# DIO_MCX_Supply.net
KiCad netlist of a schematic drawn in Altium Designer
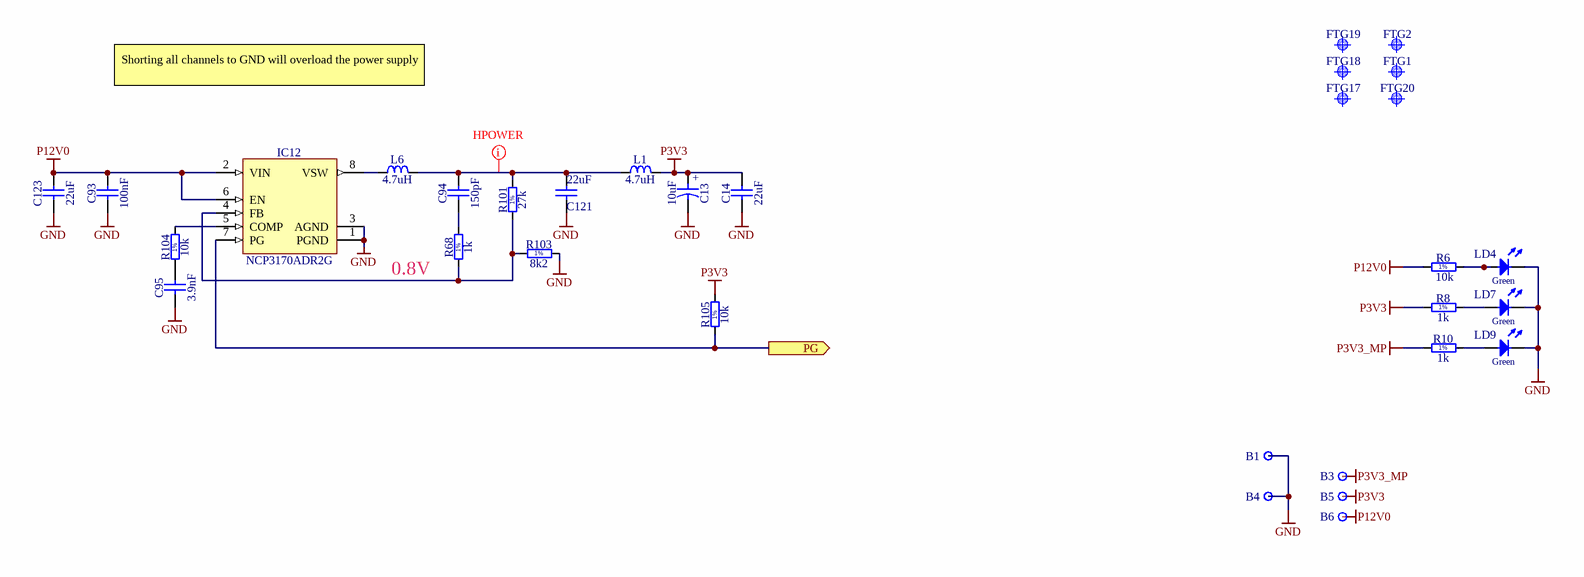
[diagram p0: DIO_MCX_Supply.SchDoc]

(export (version "E")
  (design (tool "Eeschema 10.0.6"))
  (components
    (comp (ref "B1")
      (value "Plated Hole")
      (footprint "c130h60")
      (description "Single Terminal Socket")
      (fields (field (name "PART NUMBER") "PLATED_HOLE0.6_PAD1.3") (field (name "AUTHOR") "CERN DEM MR"))
      (libsource (lib "Eletro-mechanical") (part "Single Terminal Socket"))
    )
    (comp (ref "B3")
      (value "Plated Hole")
      (footprint "c130h60")
      (description "Single Terminal Socket")
      (fields (field (name "PART NUMBER") "PLATED_HOLE0.6_PAD1.3") (field (name "AUTHOR") "CERN DEM MR"))
      (libsource (lib "Eletro-mechanical") (part "Single Terminal Socket"))
    )
    (comp (ref "B4")
      (value "Plated Hole")
      (footprint "c130h60")
      (description "Single Terminal Socket")
      (fields (field (name "PART NUMBER") "PLATED_HOLE0.6_PAD1.3") (field (name "AUTHOR") "CERN DEM MR"))
      (libsource (lib "Eletro-mechanical") (part "Single Terminal Socket"))
    )
    (comp (ref "B5")
      (value "Plated Hole")
      (footprint "c130h60")
      (description "Single Terminal Socket")
      (fields (field (name "PART NUMBER") "PLATED_HOLE0.6_PAD1.3") (field (name "AUTHOR") "CERN DEM MR"))
      (libsource (lib "Eletro-mechanical") (part "Single Terminal Socket"))
    )
    (comp (ref "B6")
      (value "Plated Hole")
      (footprint "c130h60")
      (description "Single Terminal Socket")
      (fields (field (name "PART NUMBER") "PLATED_HOLE0.6_PAD1.3") (field (name "AUTHOR") "CERN DEM MR"))
      (libsource (lib "Eletro-mechanical") (part "Single Terminal Socket"))
    )
    (comp (ref "C13")
      (value "10uF")
      (footprint "CAPAE430X540N")
      (description "Polarised capacitor")
      (fields
        (field (name "PART NUMBER") "CAE430-540_10UF_16V_20%")
        (field (name "VOLTAGE") "16V")
        (field (name "AUTHOR") "CERN DEM JLC")
      )
      (libsource (lib "Capacitors") (part "Capacitor - polarized"))
    )
    (comp (ref "C14")
      (value "22uF")
      (footprint "CAPC2012X135N")
      (description "Non-polarised capacitor")
      (fields
        (field (name "PART NUMBER") "CC0805_22UF_16V_10%_X5R")
        (field (name "VOLTAGE") "16V")
        (field (name "AUTHOR") "CERN DEM JLC")
      )
      (libsource (lib "Capacitors") (part "Capacitor - non polarized"))
    )
    (comp (ref "C93")
      (value "100nF")
      (footprint "CAPC1005X55N")
      (description "Non-polarised capacitor")
      (fields
        (field (name "PART NUMBER") "CC0402_100NF_16V_10%_X5R")
        (field (name "VOLTAGE") "16V")
        (field (name "AUTHOR") "CERN DEM JLC")
      )
      (libsource (lib "Capacitors") (part "Capacitor - non polarized"))
    )
    (comp (ref "C94")
      (value "150pF")
      (footprint "CAPC1608X87N")
      (description "Non-polarised capacitor")
      (fields
        (field (name "PART NUMBER") "CC0603_150PF_50V_1%_NP0")
        (field (name "VOLTAGE") "50V")
        (field (name "AUTHOR") "CERN DEM MR")
      )
      (libsource (lib "Capacitors") (part "Capacitor - non polarized"))
    )
    (comp (ref "C95")
      (value "3.9nF")
      (footprint "CAPC1608X87N")
      (description "Non-polarised capacitor")
      (fields
        (field (name "PART NUMBER") "CC0603_3.9NF_50V_5%_X7R")
        (field (name "VOLTAGE") "50V")
        (field (name "AUTHOR") "CERN DEM JLC")
      )
      (libsource (lib "Capacitors") (part "Capacitor - non polarized"))
    )
    (comp (ref "C121")
      (value "22uF")
      (footprint "CAPC2012X135N")
      (description "Non-polarised capacitor")
      (fields
        (field (name "PART NUMBER") "CC0805_22UF_16V_10%_X5R")
        (field (name "VOLTAGE") "16V")
        (field (name "AUTHOR") "CERN DEM JLC")
      )
      (libsource (lib "Capacitors") (part "Capacitor - non polarized"))
    )
    (comp (ref "C123")
      (value "22uF")
      (footprint "CAPC2012X135N")
      (description "Non-polarised capacitor")
      (fields
        (field (name "PART NUMBER") "CC0805_22UF_16V_10%_X5R")
        (field (name "VOLTAGE") "16V")
        (field (name "AUTHOR") "CERN DEM JLC")
      )
      (libsource (lib "Capacitors") (part "Capacitor - non polarized"))
    )
    (comp (ref "FTG1")
      (value "Use only in PCB")
      (footprint "FIDUCIAL_TOP_C100-200")
      (description "Fiducial Target")
      (fields (field (name "PART NUMBER") "FIDUCIAL_TARGET_C100-200") (field (name "AUTHOR") "CERN DEM JLC"))
      (libsource (lib "Eletro-mechanical") (part "Fiducial Target"))
    )
    (comp (ref "FTG2")
      (value "Use only in PCB")
      (footprint "FIDUCIAL_TOP_C100-200")
      (description "Fiducial Target")
      (fields (field (name "PART NUMBER") "FIDUCIAL_TARGET_C100-200") (field (name "AUTHOR") "CERN DEM JLC"))
      (libsource (lib "Eletro-mechanical") (part "Fiducial Target"))
    )
    (comp (ref "FTG17")
      (value "Use only in PCB")
      (footprint "FIDUCIAL_TOP_C100-200")
      (description "Fiducial Target")
      (fields (field (name "PART NUMBER") "FIDUCIAL_TARGET_C100-200") (field (name "AUTHOR") "CERN DEM JLC"))
      (libsource (lib "Eletro-mechanical") (part "Fiducial Target"))
    )
    (comp (ref "FTG18")
      (value "Use only in PCB")
      (footprint "FIDUCIAL_TOP_S100-200")
      (description "Fiducial Target")
      (fields (field (name "PART NUMBER") "FIDUCIAL_TARGET_S100-200") (field (name "AUTHOR") "CERN DEM JLC"))
      (libsource (lib "Eletro-mechanical") (part "Fiducial Target"))
    )
    (comp (ref "FTG19")
      (value "Use only in PCB")
      (footprint "FIDUCIAL_TOP_S100-200")
      (description "Fiducial Target")
      (fields (field (name "PART NUMBER") "FIDUCIAL_TARGET_S100-200") (field (name "AUTHOR") "CERN DEM JLC"))
      (libsource (lib "Eletro-mechanical") (part "Fiducial Target"))
    )
    (comp (ref "FTG20")
      (value "Use only in PCB")
      (footprint "FIDUCIAL_TOP_S100-200")
      (description "Fiducial Target")
      (fields (field (name "PART NUMBER") "FIDUCIAL_TARGET_S100-200") (field (name "AUTHOR") "CERN DEM JLC"))
      (libsource (lib "Eletro-mechanical") (part "Fiducial Target"))
    )
    (comp (ref "IC12")
      (value "NCP3170ADR2G")
      (footprint "SOIC127P600X175-8N")
      (description "Synchronous PWM Switching Converter")
      (fields (field (name "MANUFACTURER") "ON SEMICONDUCTOR") (field (name "AUTHOR") "CERN DEM MR"))
      (libsource (lib "ICs And Semiconductors") (part "NCP3170ADR2G"))
    )
    (comp (ref "L1")
      (value "4.7uH")
      (footprint "IND_BOURNS_SRU8043")
      (description "Power Shielded  4.7uH 30% 4.6A")
      (fields
        (field (name "PART NUMBER") "IND_4.7UH_30%_BOURNS_SRU8043")
        (field (name "POWER") "4.6A")
        (field (name "AUTHOR") "GK")
      )
      (libsource (lib "Inductors_Transformers") (part "IND_4.7UH_30%_BOURNS_SRU8043"))
    )
    (comp (ref "L6")
      (value "4.7uH")
      (footprint "IND_BOURNS_SRU8043")
      (description "Power Shielded  4.7uH 30% 4.6A")
      (fields
        (field (name "PART NUMBER") "IND_4.7UH_30%_BOURNS_SRU8043")
        (field (name "POWER") "4.6A")
        (field (name "AUTHOR") "GK")
      )
      (libsource (lib "Inductors_Transformers") (part "IND_4.7UH_30%_BOURNS_SRU8043"))
    )
    (comp (ref "LD4")
      (value "Green")
      (footprint "LED_KINGBRIGHT_KPH-1608CGCK")
      (description "LED Green 1C 2A")
      (fields
        (field (name "PART NUMBER") "LED_KINGBRIGHT_KPH-1608CGCK")
        (field (name "MANUFACTURER") "KINGBRIGHT")
        (field (name "AUTHOR") "CERN DEM JLC")
      )
      (libsource (lib "ICs And Semiconductors") (part "LED Green 1C 2A"))
    )
    (comp (ref "LD7")
      (value "Green")
      (footprint "LED_KINGBRIGHT_KPH-1608CGCK")
      (description "LED Green 1C 2A")
      (fields
        (field (name "PART NUMBER") "LED_KINGBRIGHT_KPH-1608CGCK")
        (field (name "MANUFACTURER") "KINGBRIGHT")
        (field (name "AUTHOR") "CERN DEM JLC")
      )
      (libsource (lib "ICs And Semiconductors") (part "LED Green 1C 2A"))
    )
    (comp (ref "LD9")
      (value "Green")
      (footprint "LED_KINGBRIGHT_KPH-1608CGCK")
      (description "LED Green 1C 2A")
      (fields
        (field (name "PART NUMBER") "LED_KINGBRIGHT_KPH-1608CGCK")
        (field (name "MANUFACTURER") "KINGBRIGHT")
        (field (name "AUTHOR") "CERN DEM JLC")
      )
      (libsource (lib "ICs And Semiconductors") (part "LED Green 1C 2A"))
    )
    (comp (ref "R6")
      (value "10k")
      (footprint "RESC1005X40N")
      (description "Resistor - 1%")
      (fields
        (field (name "PART NUMBER") "R0402_10K_1%_0.0625W_100PPM")
        (field (name "POWER") "0.0625W")
        (field (name "AUTHOR") "CERN DEM JLC")
      )
      (libsource (lib "Resistors") (part "Resistor - 1%"))
    )
    (comp (ref "R8")
      (value "1k")
      (footprint "RESC1005X40N")
      (description "Resistor - 1%")
      (fields
        (field (name "PART NUMBER") "R0402_1K_1%_0.0625W_100PPM")
        (field (name "POWER") "0.0625W")
        (field (name "AUTHOR") "CERN DEM JLC")
      )
      (libsource (lib "Resistors") (part "Resistor - 1%"))
    )
    (comp (ref "R10")
      (value "1k")
      (footprint "RESC1005X40N")
      (description "Resistor - 1%")
      (fields
        (field (name "PART NUMBER") "R0402_1K_1%_0.0625W_100PPM")
        (field (name "POWER") "0.0625W")
        (field (name "AUTHOR") "CERN DEM JLC")
      )
      (libsource (lib "Resistors") (part "Resistor - 1%"))
    )
    (comp (ref "R68")
      (value "1k")
      (footprint "RESC1005X40N")
      (description "Resistor - 1%")
      (fields
        (field (name "PART NUMBER") "R0402_1K_1%_0.0625W_100PPM")
        (field (name "POWER") "0.0625W")
        (field (name "AUTHOR") "CERN DEM JLC")
      )
      (libsource (lib "Resistors") (part "Resistor - 1%"))
    )
    (comp (ref "R101")
      (value "27k")
      (footprint "RESC1005X40N")
      (description "Resistor - 1%")
      (fields
        (field (name "PART NUMBER") "R0402_27K_1%_0.0625W_100PPM")
        (field (name "POWER") "0.0625W")
        (field (name "AUTHOR") "CERN DEM JLC")
      )
      (libsource (lib "Resistors") (part "Resistor - 1%"))
    )
    (comp (ref "R103")
      (value "8k2")
      (footprint "RESC1005X40N")
      (description "Resistor - 1%")
      (fields
        (field (name "PART NUMBER") "R0402_8K2_1%_0.0625W_100PPM")
        (field (name "POWER") "0.0625W")
        (field (name "AUTHOR") "CERN DEM JLC")
      )
      (libsource (lib "Resistors") (part "Resistor - 1%"))
    )
    (comp (ref "R104")
      (value "10k")
      (footprint "RESC1005X40N")
      (description "Resistor - 1%")
      (fields
        (field (name "PART NUMBER") "R0402_10K_1%_0.0625W_100PPM")
        (field (name "POWER") "0.0625W")
        (field (name "AUTHOR") "CERN DEM JLC")
      )
      (libsource (lib "Resistors") (part "Resistor - 1%"))
    )
    (comp (ref "R105")
      (value "10k")
      (footprint "RESC1005X40N")
      (description "Resistor - 1%")
      (fields
        (field (name "PART NUMBER") "R0402_10K_1%_0.0625W_100PPM")
        (field (name "POWER") "0.0625W")
        (field (name "AUTHOR") "CERN DEM JLC")
      )
      (libsource (lib "Resistors") (part "Resistor - 1%"))
    )
  )
  (nets
    (net (code "1") (name "/PG") (class "Default")
      (node (ref "IC12") (pin "7") (pinfunction "PG_7") (pintype "input"))
      (node (ref "R105") (pin "1") (pinfunction "1_1") (pintype "passive"))
    )
    (net (code "2") (name "GND") (class "Default")
      (node (ref "B1") (pin "1") (pinfunction "1_1") (pintype "bidirectional"))
      (node (ref "B4") (pin "1") (pinfunction "1_1") (pintype "bidirectional"))
      (node (ref "C121") (pin "1") (pinfunction "1_1") (pintype "passive"))
      (node (ref "C123") (pin "1") (pinfunction "1_1") (pintype "passive"))
      (node (ref "C13") (pin "2") (pinfunction "2_2") (pintype "passive"))
      (node (ref "C14") (pin "1") (pinfunction "1_1") (pintype "passive"))
      (node (ref "C93") (pin "1") (pinfunction "1_1") (pintype "passive"))
      (node (ref "C95") (pin "1") (pinfunction "1_1") (pintype "passive"))
      (node (ref "IC12") (pin "1") (pinfunction "PGND_1") (pintype "power_in"))
      (node (ref "IC12") (pin "3") (pinfunction "AGND_3") (pintype "power_in"))
      (node (ref "LD4") (pin "1") (pinfunction "C_1") (pintype "passive"))
      (node (ref "LD7") (pin "1") (pinfunction "C_1") (pintype "passive"))
      (node (ref "LD9") (pin "1") (pinfunction "C_1") (pintype "passive"))
      (node (ref "R103") (pin "2") (pinfunction "2_2") (pintype "passive"))
    )
    (net (code "3") (name "Net-(C94-Pad1)") (class "Default")
      (node (ref "C94") (pin "1") (pinfunction "1_1") (pintype "passive"))
      (node (ref "R68") (pin "2") (pinfunction "2_2") (pintype "passive"))
    )
    (net (code "4") (name "Net-(C95-Pad2)") (class "Default")
      (node (ref "C95") (pin "2") (pinfunction "2_2") (pintype "passive"))
      (node (ref "R104") (pin "1") (pinfunction "1_1") (pintype "passive"))
    )
    (net (code "5") (name "Net-(C121-Pad2)") (class "Default")
      (node (ref "C121") (pin "2") (pinfunction "2_2") (pintype "passive"))
      (node (ref "C94") (pin "2") (pinfunction "2_2") (pintype "passive"))
      (node (ref "L1") (pin "1") (pinfunction "1_1") (pintype "passive"))
      (node (ref "L6") (pin "2") (pinfunction "2_2") (pintype "passive"))
      (node (ref "R101") (pin "2") (pinfunction "2_2") (pintype "passive"))
    )
    (net (code "6") (name "Net-(IC12-COMP)") (class "Default")
      (node (ref "IC12") (pin "5") (pinfunction "COMP_5") (pintype "input"))
      (node (ref "R104") (pin "2") (pinfunction "2_2") (pintype "passive"))
    )
    (net (code "7") (name "Net-(IC12-FB)") (class "Default")
      (node (ref "IC12") (pin "4") (pinfunction "FB_4") (pintype "input"))
      (node (ref "R101") (pin "1") (pinfunction "1_1") (pintype "passive"))
      (node (ref "R103") (pin "1") (pinfunction "1_1") (pintype "passive"))
      (node (ref "R68") (pin "1") (pinfunction "1_1") (pintype "passive"))
    )
    (net (code "8") (name "Net-(IC12-VSW)") (class "Default")
      (node (ref "IC12") (pin "8") (pinfunction "VSW_8") (pintype "output"))
      (node (ref "L6") (pin "1") (pinfunction "1_1") (pintype "passive"))
    )
    (net (code "9") (name "Net-(LD4-A)") (class "Default")
      (node (ref "LD4") (pin "2") (pinfunction "A_2") (pintype "passive"))
      (node (ref "R6") (pin "1") (pinfunction "1_1") (pintype "passive"))
    )
    (net (code "10") (name "Net-(LD7-A)") (class "Default")
      (node (ref "LD7") (pin "2") (pinfunction "A_2") (pintype "passive"))
      (node (ref "R8") (pin "2") (pinfunction "2_2") (pintype "passive"))
    )
    (net (code "11") (name "Net-(LD9-A)") (class "Default")
      (node (ref "LD9") (pin "2") (pinfunction "A_2") (pintype "passive"))
      (node (ref "R10") (pin "2") (pinfunction "2_2") (pintype "passive"))
    )
    (net (code "12") (name "P3V3") (class "Default")
      (node (ref "B5") (pin "1") (pinfunction "1_1") (pintype "bidirectional"))
      (node (ref "C13") (pin "1") (pinfunction "1_1") (pintype "passive"))
      (node (ref "C14") (pin "2") (pinfunction "2_2") (pintype "passive"))
      (node (ref "L1") (pin "2") (pinfunction "2_2") (pintype "passive"))
      (node (ref "R105") (pin "2") (pinfunction "2_2") (pintype "passive"))
      (node (ref "R8") (pin "1") (pinfunction "1_1") (pintype "passive"))
    )
    (net (code "13") (name "P3V3_MP") (class "Default")
      (node (ref "B3") (pin "1") (pinfunction "1_1") (pintype "bidirectional"))
      (node (ref "R10") (pin "1") (pinfunction "1_1") (pintype "passive"))
    )
    (net (code "14") (name "P12V0") (class "Default")
      (node (ref "B6") (pin "1") (pinfunction "1_1") (pintype "bidirectional"))
      (node (ref "C123") (pin "2") (pinfunction "2_2") (pintype "passive"))
      (node (ref "C93") (pin "2") (pinfunction "2_2") (pintype "passive"))
      (node (ref "IC12") (pin "2") (pinfunction "VIN_2") (pintype "input"))
      (node (ref "IC12") (pin "6") (pinfunction "EN_6") (pintype "input"))
      (node (ref "R6") (pin "2") (pinfunction "2_2") (pintype "passive"))
    )
  )
)
